# BinaryClock_LEDs.net
KiCad netlist of a schematic drawn in Altium Designer
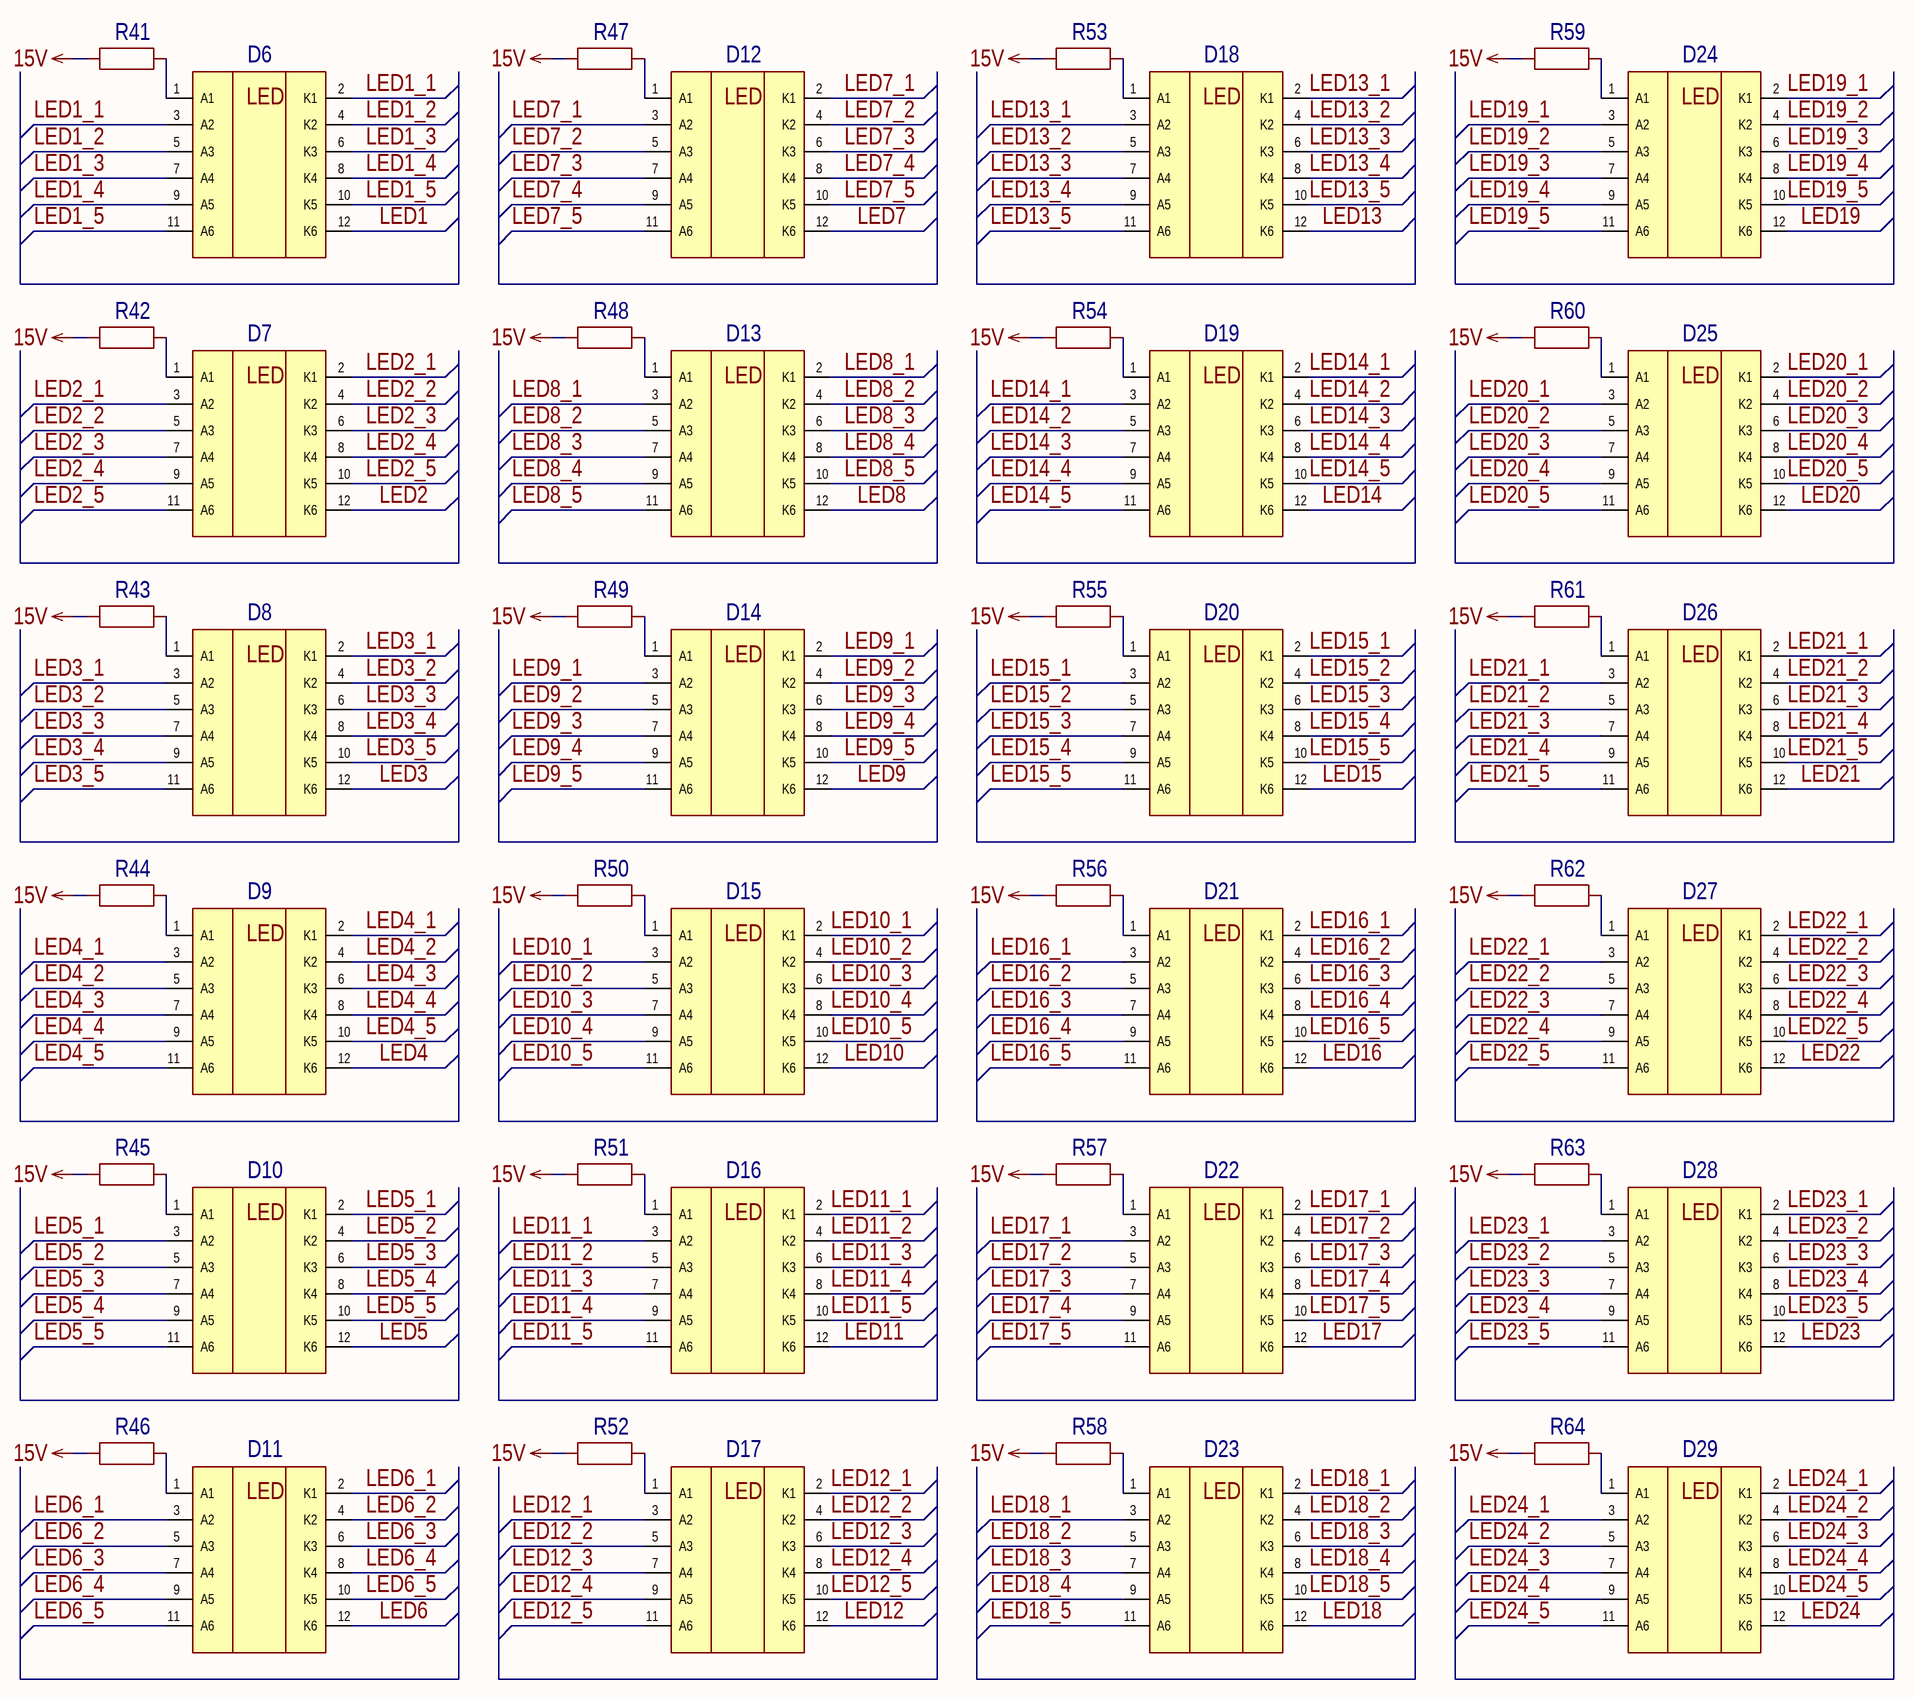
[diagram p0: BinaryClock_LEDs.SchDoc]

(export (version "E")
  (design (tool "Eeschema 10.0.6"))
  (components
    (comp (ref "D6")
      (value "DLA/6ID")
      (footprint "DLA/6ID")
      (description "20mm BIG LAMP")
      (fields (field (name "MANUFACTURER") "Kingbright"))
      (libsource (lib "Devices") (part "DLA"))
    )
    (comp (ref "D7")
      (value "DLA/6ID")
      (footprint "DLA/6ID")
      (description "20mm BIG LAMP")
      (fields (field (name "MANUFACTURER") "Kingbright"))
      (libsource (lib "Devices") (part "DLA"))
    )
    (comp (ref "D8")
      (value "DLA/6ID")
      (footprint "DLA/6ID")
      (description "20mm BIG LAMP")
      (fields (field (name "MANUFACTURER") "Kingbright"))
      (libsource (lib "Devices") (part "DLA"))
    )
    (comp (ref "D9")
      (value "DLA/6ID")
      (footprint "DLA/6ID")
      (description "20mm BIG LAMP")
      (fields (field (name "MANUFACTURER") "Kingbright"))
      (libsource (lib "Devices") (part "DLA"))
    )
    (comp (ref "D10")
      (value "DLA/6ID")
      (footprint "DLA/6ID")
      (description "20mm BIG LAMP")
      (fields (field (name "MANUFACTURER") "Kingbright"))
      (libsource (lib "Devices") (part "DLA"))
    )
    (comp (ref "D11")
      (value "DLA/6ID")
      (footprint "DLA/6ID")
      (description "20mm BIG LAMP")
      (fields (field (name "MANUFACTURER") "Kingbright"))
      (libsource (lib "Devices") (part "DLA"))
    )
    (comp (ref "D12")
      (value "DLA/6ID")
      (footprint "DLA/6ID")
      (description "20mm BIG LAMP")
      (fields (field (name "MANUFACTURER") "Kingbright"))
      (libsource (lib "Devices") (part "DLA"))
    )
    (comp (ref "D13")
      (value "DLA/6ID")
      (footprint "DLA/6ID")
      (description "20mm BIG LAMP")
      (fields (field (name "MANUFACTURER") "Kingbright"))
      (libsource (lib "Devices") (part "DLA"))
    )
    (comp (ref "D14")
      (value "DLA/6YD")
      (footprint "DLA/6YD")
      (description "20mm BIG LAMP")
      (fields (field (name "MANUFACTURER") "Kingbright"))
      (libsource (lib "Devices") (part "DLA"))
    )
    (comp (ref "D15")
      (value "DLA/6YD")
      (footprint "DLA/6YD")
      (description "20mm BIG LAMP")
      (fields (field (name "MANUFACTURER") "Kingbright"))
      (libsource (lib "Devices") (part "DLA"))
    )
    (comp (ref "D16")
      (value "DLA/6YD")
      (footprint "DLA/6YD")
      (description "20mm BIG LAMP")
      (fields (field (name "MANUFACTURER") "Kingbright"))
      (libsource (lib "Devices") (part "DLA"))
    )
    (comp (ref "D17")
      (value "DLA/6YD")
      (footprint "DLA/6YD")
      (description "20mm BIG LAMP")
      (fields (field (name "MANUFACTURER") "Kingbright"))
      (libsource (lib "Devices") (part "DLA"))
    )
    (comp (ref "D18")
      (value "DLA/6YD")
      (footprint "DLA/6YD")
      (description "20mm BIG LAMP")
      (fields (field (name "MANUFACTURER") "Kingbright"))
      (libsource (lib "Devices") (part "DLA"))
    )
    (comp (ref "D19")
      (value "DLA/6YD")
      (footprint "DLA/6YD")
      (description "20mm BIG LAMP")
      (fields (field (name "MANUFACTURER") "Kingbright"))
      (libsource (lib "Devices") (part "DLA"))
    )
    (comp (ref "D20")
      (value "DLA/6YD")
      (footprint "DLA/6YD")
      (description "20mm BIG LAMP")
      (fields (field (name "MANUFACTURER") "Kingbright"))
      (libsource (lib "Devices") (part "DLA"))
    )
    (comp (ref "D21")
      (value "DLA/6YD")
      (footprint "DLA/6YD")
      (description "20mm BIG LAMP")
      (fields (field (name "MANUFACTURER") "Kingbright"))
      (libsource (lib "Devices") (part "DLA"))
    )
    (comp (ref "D22")
      (value "DLA/6SGD")
      (footprint "DLA/6GD")
      (description "20mm BIG LAMP")
      (fields (field (name "MANUFACTURER") "Kingbright"))
      (libsource (lib "Devices") (part "DLA"))
    )
    (comp (ref "D23")
      (value "DLA/6SGD")
      (footprint "DLA/6GD")
      (description "20mm BIG LAMP")
      (fields (field (name "MANUFACTURER") "Kingbright"))
      (libsource (lib "Devices") (part "DLA"))
    )
    (comp (ref "D24")
      (value "DLA/6SGD")
      (footprint "DLA/6GD")
      (description "20mm BIG LAMP")
      (fields (field (name "MANUFACTURER") "Kingbright"))
      (libsource (lib "Devices") (part "DLA"))
    )
    (comp (ref "D25")
      (value "DLA/6SGD")
      (footprint "DLA/6GD")
      (description "20mm BIG LAMP")
      (fields (field (name "MANUFACTURER") "Kingbright"))
      (libsource (lib "Devices") (part "DLA"))
    )
    (comp (ref "D26")
      (value "DLA/6SGD")
      (footprint "DLA/6GD")
      (description "20mm BIG LAMP")
      (fields (field (name "MANUFACTURER") "Kingbright"))
      (libsource (lib "Devices") (part "DLA"))
    )
    (comp (ref "D27")
      (value "DLA/6SGD")
      (footprint "DLA/6GD")
      (description "20mm BIG LAMP")
      (fields (field (name "MANUFACTURER") "Kingbright"))
      (libsource (lib "Devices") (part "DLA"))
    )
    (comp (ref "D28")
      (value "DLA/6SGD")
      (footprint "DLA/6GD")
      (description "20mm BIG LAMP")
      (fields (field (name "MANUFACTURER") "Kingbright"))
      (libsource (lib "Devices") (part "DLA"))
    )
    (comp (ref "D29")
      (value "DLA/6SGD")
      (footprint "DLA/6GD")
      (description "20mm BIG LAMP")
      (fields (field (name "MANUFACTURER") "Kingbright"))
      (libsource (lib "Devices") (part "DLA"))
    )
    (comp (ref "R41")
      (value "0805±1 %-? kOhm")
      (footprint "SMD-0805-RES")
      (description "Resistor")
      (libsource (lib "Passive,Diodes") (part "Res"))
    )
    (comp (ref "R42")
      (value "0805±1 %-? kOhm")
      (footprint "SMD-0805-RES")
      (description "Resistor")
      (libsource (lib "Passive,Diodes") (part "Res"))
    )
    (comp (ref "R43")
      (value "0805±1 %-? kOhm")
      (footprint "SMD-0805-RES")
      (description "Resistor")
      (libsource (lib "Passive,Diodes") (part "Res"))
    )
    (comp (ref "R44")
      (value "0805±1 %-? kOhm")
      (footprint "SMD-0805-RES")
      (description "Resistor")
      (libsource (lib "Passive,Diodes") (part "Res"))
    )
    (comp (ref "R45")
      (value "0805±1 %-? kOhm")
      (footprint "SMD-0805-RES")
      (description "Resistor")
      (libsource (lib "Passive,Diodes") (part "Res"))
    )
    (comp (ref "R46")
      (value "0805±1 %-? kOhm")
      (footprint "SMD-0805-RES")
      (description "Resistor")
      (libsource (lib "Passive,Diodes") (part "Res"))
    )
    (comp (ref "R47")
      (value "0805±1 %-? kOhm")
      (footprint "SMD-0805-RES")
      (description "Resistor")
      (libsource (lib "Passive,Diodes") (part "Res"))
    )
    (comp (ref "R48")
      (value "0805±1 %-? kOhm")
      (footprint "SMD-0805-RES")
      (description "Resistor")
      (libsource (lib "Passive,Diodes") (part "Res"))
    )
    (comp (ref "R49")
      (value "0805±1 %-? kOhm")
      (footprint "SMD-0805-RES")
      (description "Resistor")
      (libsource (lib "Passive,Diodes") (part "Res"))
    )
    (comp (ref "R50")
      (value "0805±1 %-? kOhm")
      (footprint "SMD-0805-RES")
      (description "Resistor")
      (libsource (lib "Passive,Diodes") (part "Res"))
    )
    (comp (ref "R51")
      (value "0805±1 %-? kOhm")
      (footprint "SMD-0805-RES")
      (description "Resistor")
      (libsource (lib "Passive,Diodes") (part "Res"))
    )
    (comp (ref "R52")
      (value "0805±1 %-? kOhm")
      (footprint "SMD-0805-RES")
      (description "Resistor")
      (libsource (lib "Passive,Diodes") (part "Res"))
    )
    (comp (ref "R53")
      (value "0805±1 %-? kOhm")
      (footprint "SMD-0805-RES")
      (description "Resistor")
      (libsource (lib "Passive,Diodes") (part "Res"))
    )
    (comp (ref "R54")
      (value "0805±1 %-? kOhm")
      (footprint "SMD-0805-RES")
      (description "Resistor")
      (libsource (lib "Passive,Diodes") (part "Res"))
    )
    (comp (ref "R55")
      (value "0805±1 %-? kOhm")
      (footprint "SMD-0805-RES")
      (description "Resistor")
      (libsource (lib "Passive,Diodes") (part "Res"))
    )
    (comp (ref "R56")
      (value "0805±1 %-? kOhm")
      (footprint "SMD-0805-RES")
      (description "Resistor")
      (libsource (lib "Passive,Diodes") (part "Res"))
    )
    (comp (ref "R57")
      (value "0805±1 %-? kOhm")
      (footprint "SMD-0805-RES")
      (description "Resistor")
      (libsource (lib "Passive,Diodes") (part "Res"))
    )
    (comp (ref "R58")
      (value "0805±1 %-? kOhm")
      (footprint "SMD-0805-RES")
      (description "Resistor")
      (libsource (lib "Passive,Diodes") (part "Res"))
    )
    (comp (ref "R59")
      (value "0805±1 %-? kOhm")
      (footprint "SMD-0805-RES")
      (description "Resistor")
      (libsource (lib "Passive,Diodes") (part "Res"))
    )
    (comp (ref "R60")
      (value "0805±1 %-? kOhm")
      (footprint "SMD-0805-RES")
      (description "Resistor")
      (libsource (lib "Passive,Diodes") (part "Res"))
    )
    (comp (ref "R61")
      (value "0805±1 %-? kOhm")
      (footprint "SMD-0805-RES")
      (description "Resistor")
      (libsource (lib "Passive,Diodes") (part "Res"))
    )
    (comp (ref "R62")
      (value "0805±1 %-? kOhm")
      (footprint "SMD-0805-RES")
      (description "Resistor")
      (libsource (lib "Passive,Diodes") (part "Res"))
    )
    (comp (ref "R63")
      (value "0805±1 %-? kOhm")
      (footprint "SMD-0805-RES")
      (description "Resistor")
      (libsource (lib "Passive,Diodes") (part "Res"))
    )
    (comp (ref "R64")
      (value "0805±1 %-? kOhm")
      (footprint "SMD-0805-RES")
      (description "Resistor")
      (libsource (lib "Passive,Diodes") (part "Res"))
    )
  )
  (nets
    (net (code "1") (name "/LED1") (class "Default")
      (node (ref "D6") (pin "12") (pinfunction "K6_12") (pintype "passive"))
    )
    (net (code "2") (name "/LED1_1") (class "Default")
      (node (ref "D6") (pin "2") (pinfunction "K1_2") (pintype "passive"))
      (node (ref "D6") (pin "3") (pinfunction "A2_3") (pintype "passive"))
    )
    (net (code "3") (name "/LED1_2") (class "Default")
      (node (ref "D6") (pin "4") (pinfunction "K2_4") (pintype "passive"))
      (node (ref "D6") (pin "5") (pinfunction "A3_5") (pintype "passive"))
    )
    (net (code "4") (name "/LED1_3") (class "Default")
      (node (ref "D6") (pin "6") (pinfunction "K3_6") (pintype "passive"))
      (node (ref "D6") (pin "7") (pinfunction "A4_7") (pintype "passive"))
    )
    (net (code "5") (name "/LED1_4") (class "Default")
      (node (ref "D6") (pin "8") (pinfunction "K4_8") (pintype "passive"))
      (node (ref "D6") (pin "9") (pinfunction "A5_9") (pintype "passive"))
    )
    (net (code "6") (name "/LED1_5") (class "Default")
      (node (ref "D6") (pin "10") (pinfunction "K5_10") (pintype "passive"))
      (node (ref "D6") (pin "11") (pinfunction "A6_11") (pintype "passive"))
    )
    (net (code "7") (name "/LED2") (class "Default")
      (node (ref "D7") (pin "12") (pinfunction "K6_12") (pintype "passive"))
    )
    (net (code "8") (name "/LED2_1") (class "Default")
      (node (ref "D7") (pin "2") (pinfunction "K1_2") (pintype "passive"))
      (node (ref "D7") (pin "3") (pinfunction "A2_3") (pintype "passive"))
    )
    (net (code "9") (name "/LED2_2") (class "Default")
      (node (ref "D7") (pin "4") (pinfunction "K2_4") (pintype "passive"))
      (node (ref "D7") (pin "5") (pinfunction "A3_5") (pintype "passive"))
    )
    (net (code "10") (name "/LED2_3") (class "Default")
      (node (ref "D7") (pin "6") (pinfunction "K3_6") (pintype "passive"))
      (node (ref "D7") (pin "7") (pinfunction "A4_7") (pintype "passive"))
    )
    (net (code "11") (name "/LED2_4") (class "Default")
      (node (ref "D7") (pin "8") (pinfunction "K4_8") (pintype "passive"))
      (node (ref "D7") (pin "9") (pinfunction "A5_9") (pintype "passive"))
    )
    (net (code "12") (name "/LED2_5") (class "Default")
      (node (ref "D7") (pin "10") (pinfunction "K5_10") (pintype "passive"))
      (node (ref "D7") (pin "11") (pinfunction "A6_11") (pintype "passive"))
    )
    (net (code "13") (name "/LED3") (class "Default")
      (node (ref "D8") (pin "12") (pinfunction "K6_12") (pintype "passive"))
    )
    (net (code "14") (name "/LED3_1") (class "Default")
      (node (ref "D8") (pin "2") (pinfunction "K1_2") (pintype "passive"))
      (node (ref "D8") (pin "3") (pinfunction "A2_3") (pintype "passive"))
    )
    (net (code "15") (name "/LED3_2") (class "Default")
      (node (ref "D8") (pin "4") (pinfunction "K2_4") (pintype "passive"))
      (node (ref "D8") (pin "5") (pinfunction "A3_5") (pintype "passive"))
    )
    (net (code "16") (name "/LED3_3") (class "Default")
      (node (ref "D8") (pin "6") (pinfunction "K3_6") (pintype "passive"))
      (node (ref "D8") (pin "7") (pinfunction "A4_7") (pintype "passive"))
    )
    (net (code "17") (name "/LED3_4") (class "Default")
      (node (ref "D8") (pin "8") (pinfunction "K4_8") (pintype "passive"))
      (node (ref "D8") (pin "9") (pinfunction "A5_9") (pintype "passive"))
    )
    (net (code "18") (name "/LED3_5") (class "Default")
      (node (ref "D8") (pin "10") (pinfunction "K5_10") (pintype "passive"))
      (node (ref "D8") (pin "11") (pinfunction "A6_11") (pintype "passive"))
    )
    (net (code "19") (name "/LED4") (class "Default")
      (node (ref "D9") (pin "12") (pinfunction "K6_12") (pintype "passive"))
    )
    (net (code "20") (name "/LED4_1") (class "Default")
      (node (ref "D9") (pin "2") (pinfunction "K1_2") (pintype "passive"))
      (node (ref "D9") (pin "3") (pinfunction "A2_3") (pintype "passive"))
    )
    (net (code "21") (name "/LED4_2") (class "Default")
      (node (ref "D9") (pin "4") (pinfunction "K2_4") (pintype "passive"))
      (node (ref "D9") (pin "5") (pinfunction "A3_5") (pintype "passive"))
    )
    (net (code "22") (name "/LED4_3") (class "Default")
      (node (ref "D9") (pin "6") (pinfunction "K3_6") (pintype "passive"))
      (node (ref "D9") (pin "7") (pinfunction "A4_7") (pintype "passive"))
    )
    (net (code "23") (name "/LED4_4") (class "Default")
      (node (ref "D9") (pin "8") (pinfunction "K4_8") (pintype "passive"))
      (node (ref "D9") (pin "9") (pinfunction "A5_9") (pintype "passive"))
    )
    (net (code "24") (name "/LED4_5") (class "Default")
      (node (ref "D9") (pin "10") (pinfunction "K5_10") (pintype "passive"))
      (node (ref "D9") (pin "11") (pinfunction "A6_11") (pintype "passive"))
    )
    (net (code "25") (name "/LED5") (class "Default")
      (node (ref "D10") (pin "12") (pinfunction "K6_12") (pintype "passive"))
    )
    (net (code "26") (name "/LED5_1") (class "Default")
      (node (ref "D10") (pin "2") (pinfunction "K1_2") (pintype "passive"))
      (node (ref "D10") (pin "3") (pinfunction "A2_3") (pintype "passive"))
    )
    (net (code "27") (name "/LED5_2") (class "Default")
      (node (ref "D10") (pin "4") (pinfunction "K2_4") (pintype "passive"))
      (node (ref "D10") (pin "5") (pinfunction "A3_5") (pintype "passive"))
    )
    (net (code "28") (name "/LED5_3") (class "Default")
      (node (ref "D10") (pin "6") (pinfunction "K3_6") (pintype "passive"))
      (node (ref "D10") (pin "7") (pinfunction "A4_7") (pintype "passive"))
    )
    (net (code "29") (name "/LED5_4") (class "Default")
      (node (ref "D10") (pin "8") (pinfunction "K4_8") (pintype "passive"))
      (node (ref "D10") (pin "9") (pinfunction "A5_9") (pintype "passive"))
    )
    (net (code "30") (name "/LED5_5") (class "Default")
      (node (ref "D10") (pin "10") (pinfunction "K5_10") (pintype "passive"))
      (node (ref "D10") (pin "11") (pinfunction "A6_11") (pintype "passive"))
    )
    (net (code "31") (name "/LED6") (class "Default")
      (node (ref "D11") (pin "12") (pinfunction "K6_12") (pintype "passive"))
    )
    (net (code "32") (name "/LED6_1") (class "Default")
      (node (ref "D11") (pin "2") (pinfunction "K1_2") (pintype "passive"))
      (node (ref "D11") (pin "3") (pinfunction "A2_3") (pintype "passive"))
    )
    (net (code "33") (name "/LED6_2") (class "Default")
      (node (ref "D11") (pin "4") (pinfunction "K2_4") (pintype "passive"))
      (node (ref "D11") (pin "5") (pinfunction "A3_5") (pintype "passive"))
    )
    (net (code "34") (name "/LED6_3") (class "Default")
      (node (ref "D11") (pin "6") (pinfunction "K3_6") (pintype "passive"))
      (node (ref "D11") (pin "7") (pinfunction "A4_7") (pintype "passive"))
    )
    (net (code "35") (name "/LED6_4") (class "Default")
      (node (ref "D11") (pin "8") (pinfunction "K4_8") (pintype "passive"))
      (node (ref "D11") (pin "9") (pinfunction "A5_9") (pintype "passive"))
    )
    (net (code "36") (name "/LED6_5") (class "Default")
      (node (ref "D11") (pin "10") (pinfunction "K5_10") (pintype "passive"))
      (node (ref "D11") (pin "11") (pinfunction "A6_11") (pintype "passive"))
    )
    (net (code "37") (name "/LED7") (class "Default")
      (node (ref "D12") (pin "12") (pinfunction "K6_12") (pintype "passive"))
    )
    (net (code "38") (name "/LED7_1") (class "Default")
      (node (ref "D12") (pin "2") (pinfunction "K1_2") (pintype "passive"))
      (node (ref "D12") (pin "3") (pinfunction "A2_3") (pintype "passive"))
    )
    (net (code "39") (name "/LED7_2") (class "Default")
      (node (ref "D12") (pin "4") (pinfunction "K2_4") (pintype "passive"))
      (node (ref "D12") (pin "5") (pinfunction "A3_5") (pintype "passive"))
    )
    (net (code "40") (name "/LED7_3") (class "Default")
      (node (ref "D12") (pin "6") (pinfunction "K3_6") (pintype "passive"))
      (node (ref "D12") (pin "7") (pinfunction "A4_7") (pintype "passive"))
    )
    (net (code "41") (name "/LED7_4") (class "Default")
      (node (ref "D12") (pin "8") (pinfunction "K4_8") (pintype "passive"))
      (node (ref "D12") (pin "9") (pinfunction "A5_9") (pintype "passive"))
    )
    (net (code "42") (name "/LED7_5") (class "Default")
      (node (ref "D12") (pin "10") (pinfunction "K5_10") (pintype "passive"))
      (node (ref "D12") (pin "11") (pinfunction "A6_11") (pintype "passive"))
    )
    (net (code "43") (name "/LED8") (class "Default")
      (node (ref "D13") (pin "12") (pinfunction "K6_12") (pintype "passive"))
    )
    (net (code "44") (name "/LED8_1") (class "Default")
      (node (ref "D13") (pin "2") (pinfunction "K1_2") (pintype "passive"))
      (node (ref "D13") (pin "3") (pinfunction "A2_3") (pintype "passive"))
    )
    (net (code "45") (name "/LED8_2") (class "Default")
      (node (ref "D13") (pin "4") (pinfunction "K2_4") (pintype "passive"))
      (node (ref "D13") (pin "5") (pinfunction "A3_5") (pintype "passive"))
    )
    (net (code "46") (name "/LED8_3") (class "Default")
      (node (ref "D13") (pin "6") (pinfunction "K3_6") (pintype "passive"))
      (node (ref "D13") (pin "7") (pinfunction "A4_7") (pintype "passive"))
    )
    (net (code "47") (name "/LED8_4") (class "Default")
      (node (ref "D13") (pin "8") (pinfunction "K4_8") (pintype "passive"))
      (node (ref "D13") (pin "9") (pinfunction "A5_9") (pintype "passive"))
    )
    (net (code "48") (name "/LED8_5") (class "Default")
      (node (ref "D13") (pin "10") (pinfunction "K5_10") (pintype "passive"))
      (node (ref "D13") (pin "11") (pinfunction "A6_11") (pintype "passive"))
    )
    (net (code "49") (name "/LED9") (class "Default")
      (node (ref "D14") (pin "12") (pinfunction "K6_12") (pintype "passive"))
    )
    (net (code "50") (name "/LED9_1") (class "Default")
      (node (ref "D14") (pin "2") (pinfunction "K1_2") (pintype "passive"))
      (node (ref "D14") (pin "3") (pinfunction "A2_3") (pintype "passive"))
    )
    (net (code "51") (name "/LED9_2") (class "Default")
      (node (ref "D14") (pin "4") (pinfunction "K2_4") (pintype "passive"))
      (node (ref "D14") (pin "5") (pinfunction "A3_5") (pintype "passive"))
    )
    (net (code "52") (name "/LED9_3") (class "Default")
      (node (ref "D14") (pin "6") (pinfunction "K3_6") (pintype "passive"))
      (node (ref "D14") (pin "7") (pinfunction "A4_7") (pintype "passive"))
    )
    (net (code "53") (name "/LED9_4") (class "Default")
      (node (ref "D14") (pin "8") (pinfunction "K4_8") (pintype "passive"))
      (node (ref "D14") (pin "9") (pinfunction "A5_9") (pintype "passive"))
    )
    (net (code "54") (name "/LED9_5") (class "Default")
      (node (ref "D14") (pin "10") (pinfunction "K5_10") (pintype "passive"))
      (node (ref "D14") (pin "11") (pinfunction "A6_11") (pintype "passive"))
    )
    (net (code "55") (name "/LED10") (class "Default")
      (node (ref "D15") (pin "12") (pinfunction "K6_12") (pintype "passive"))
    )
    (net (code "56") (name "/LED10_1") (class "Default")
      (node (ref "D15") (pin "2") (pinfunction "K1_2") (pintype "passive"))
      (node (ref "D15") (pin "3") (pinfunction "A2_3") (pintype "passive"))
    )
    (net (code "57") (name "/LED10_2") (class "Default")
      (node (ref "D15") (pin "4") (pinfunction "K2_4") (pintype "passive"))
      (node (ref "D15") (pin "5") (pinfunction "A3_5") (pintype "passive"))
    )
    (net (code "58") (name "/LED10_3") (class "Default")
      (node (ref "D15") (pin "6") (pinfunction "K3_6") (pintype "passive"))
      (node (ref "D15") (pin "7") (pinfunction "A4_7") (pintype "passive"))
    )
    (net (code "59") (name "/LED10_4") (class "Default")
      (node (ref "D15") (pin "8") (pinfunction "K4_8") (pintype "passive"))
      (node (ref "D15") (pin "9") (pinfunction "A5_9") (pintype "passive"))
    )
    (net (code "60") (name "/LED10_5") (class "Default")
      (node (ref "D15") (pin "10") (pinfunction "K5_10") (pintype "passive"))
      (node (ref "D15") (pin "11") (pinfunction "A6_11") (pintype "passive"))
    )
    (net (code "61") (name "/LED11") (class "Default")
      (node (ref "D16") (pin "12") (pinfunction "K6_12") (pintype "passive"))
    )
    (net (code "62") (name "/LED11_1") (class "Default")
      (node (ref "D16") (pin "2") (pinfunction "K1_2") (pintype "passive"))
      (node (ref "D16") (pin "3") (pinfunction "A2_3") (pintype "passive"))
    )
    (net (code "63") (name "/LED11_2") (class "Default")
      (node (ref "D16") (pin "4") (pinfunction "K2_4") (pintype "passive"))
      (node (ref "D16") (pin "5") (pinfunction "A3_5") (pintype "passive"))
    )
    (net (code "64") (name "/LED11_3") (class "Default")
      (node (ref "D16") (pin "6") (pinfunction "K3_6") (pintype "passive"))
      (node (ref "D16") (pin "7") (pinfunction "A4_7") (pintype "passive"))
    )
    (net (code "65") (name "/LED11_4") (class "Default")
      (node (ref "D16") (pin "8") (pinfunction "K4_8") (pintype "passive"))
      (node (ref "D16") (pin "9") (pinfunction "A5_9") (pintype "passive"))
    )
    (net (code "66") (name "/LED11_5") (class "Default")
      (node (ref "D16") (pin "10") (pinfunction "K5_10") (pintype "passive"))
      (node (ref "D16") (pin "11") (pinfunction "A6_11") (pintype "passive"))
    )
    (net (code "67") (name "/LED12") (class "Default")
      (node (ref "D17") (pin "12") (pinfunction "K6_12") (pintype "passive"))
    )
    (net (code "68") (name "/LED12_1") (class "Default")
      (node (ref "D17") (pin "2") (pinfunction "K1_2") (pintype "passive"))
      (node (ref "D17") (pin "3") (pinfunction "A2_3") (pintype "passive"))
    )
    (net (code "69") (name "/LED12_2") (class "Default")
      (node (ref "D17") (pin "4") (pinfunction "K2_4") (pintype "passive"))
      (node (ref "D17") (pin "5") (pinfunction "A3_5") (pintype "passive"))
    )
    (net (code "70") (name "/LED12_3") (class "Default")
      (node (ref "D17") (pin "6") (pinfunction "K3_6") (pintype "passive"))
      (node (ref "D17") (pin "7") (pinfunction "A4_7") (pintype "passive"))
    )
    (net (code "71") (name "/LED12_4") (class "Default")
      (node (ref "D17") (pin "8") (pinfunction "K4_8") (pintype "passive"))
      (node (ref "D17") (pin "9") (pinfunction "A5_9") (pintype "passive"))
    )
    (net (code "72") (name "/LED12_5") (class "Default")
      (node (ref "D17") (pin "10") (pinfunction "K5_10") (pintype "passive"))
      (node (ref "D17") (pin "11") (pinfunction "A6_11") (pintype "passive"))
    )
    (net (code "73") (name "/LED13") (class "Default")
      (node (ref "D18") (pin "12") (pinfunction "K6_12") (pintype "passive"))
    )
    (net (code "74") (name "/LED13_1") (class "Default")
      (node (ref "D18") (pin "2") (pinfunction "K1_2") (pintype "passive"))
      (node (ref "D18") (pin "3") (pinfunction "A2_3") (pintype "passive"))
    )
    (net (code "75") (name "/LED13_2") (class "Default")
      (node (ref "D18") (pin "4") (pinfunction "K2_4") (pintype "passive"))
      (node (ref "D18") (pin "5") (pinfunction "A3_5") (pintype "passive"))
    )
    (net (code "76") (name "/LED13_3") (class "Default")
      (node (ref "D18") (pin "6") (pinfunction "K3_6") (pintype "passive"))
      (node (ref "D18") (pin "7") (pinfunction "A4_7") (pintype "passive"))
    )
    (net (code "77") (name "/LED13_4") (class "Default")
      (node (ref "D18") (pin "8") (pinfunction "K4_8") (pintype "passive"))
      (node (ref "D18") (pin "9") (pinfunction "A5_9") (pintype "passive"))
    )
    (net (code "78") (name "/LED13_5") (class "Default")
      (node (ref "D18") (pin "10") (pinfunction "K5_10") (pintype "passive"))
      (node (ref "D18") (pin "11") (pinfunction "A6_11") (pintype "passive"))
    )
    (net (code "79") (name "/LED14") (class "Default")
      (node (ref "D19") (pin "12") (pinfunction "K6_12") (pintype "passive"))
    )
    (net (code "80") (name "/LED14_1") (class "Default")
      (node (ref "D19") (pin "2") (pinfunction "K1_2") (pintype "passive"))
      (node (ref "D19") (pin "3") (pinfunction "A2_3") (pintype "passive"))
    )
    (net (code "81") (name "/LED14_2") (class "Default")
      (node (ref "D19") (pin "4") (pinfunction "K2_4") (pintype "passive"))
      (node (ref "D19") (pin "5") (pinfunction "A3_5") (pintype "passive"))
    )
    (net (code "82") (name "/LED14_3") (class "Default")
      (node (ref "D19") (pin "6") (pinfunction "K3_6") (pintype "passive"))
      (node (ref "D19") (pin "7") (pinfunction "A4_7") (pintype "passive"))
    )
    (net (code "83") (name "/LED14_4") (class "Default")
      (node (ref "D19") (pin "8") (pinfunction "K4_8") (pintype "passive"))
      (node (ref "D19") (pin "9") (pinfunction "A5_9") (pintype "passive"))
    )
    (net (code "84") (name "/LED14_5") (class "Default")
      (node (ref "D19") (pin "10") (pinfunction "K5_10") (pintype "passive"))
      (node (ref "D19") (pin "11") (pinfunction "A6_11") (pintype "passive"))
    )
    (net (code "85") (name "/LED15") (class "Default")
      (node (ref "D20") (pin "12") (pinfunction "K6_12") (pintype "passive"))
    )
    (net (code "86") (name "/LED15_1") (class "Default")
      (node (ref "D20") (pin "2") (pinfunction "K1_2") (pintype "passive"))
      (node (ref "D20") (pin "3") (pinfunction "A2_3") (pintype "passive"))
    )
    (net (code "87") (name "/LED15_2") (class "Default")
      (node (ref "D20") (pin "4") (pinfunction "K2_4") (pintype "passive"))
      (node (ref "D20") (pin "5") (pinfunction "A3_5") (pintype "passive"))
    )
    (net (code "88") (name "/LED15_3") (class "Default")
      (node (ref "D20") (pin "6") (pinfunction "K3_6") (pintype "passive"))
      (node (ref "D20") (pin "7") (pinfunction "A4_7") (pintype "passive"))
    )
    (net (code "89") (name "/LED15_4") (class "Default")
      (node (ref "D20") (pin "8") (pinfunction "K4_8") (pintype "passive"))
      (node (ref "D20") (pin "9") (pinfunction "A5_9") (pintype "passive"))
    )
    (net (code "90") (name "/LED15_5") (class "Default")
      (node (ref "D20") (pin "10") (pinfunction "K5_10") (pintype "passive"))
      (node (ref "D20") (pin "11") (pinfunction "A6_11") (pintype "passive"))
    )
    (net (code "91") (name "/LED16") (class "Default")
      (node (ref "D21") (pin "12") (pinfunction "K6_12") (pintype "passive"))
    )
    (net (code "92") (name "/LED16_1") (class "Default")
      (node (ref "D21") (pin "2") (pinfunction "K1_2") (pintype "passive"))
      (node (ref "D21") (pin "3") (pinfunction "A2_3") (pintype "passive"))
    )
    (net (code "93") (name "/LED16_2") (class "Default")
      (node (ref "D21") (pin "4") (pinfunction "K2_4") (pintype "passive"))
      (node (ref "D21") (pin "5") (pinfunction "A3_5") (pintype "passive"))
    )
    (net (code "94") (name "/LED16_3") (class "Default")
      (node (ref "D21") (pin "6") (pinfunction "K3_6") (pintype "passive"))
      (node (ref "D21") (pin "7") (pinfunction "A4_7") (pintype "passive"))
    )
    (net (code "95") (name "/LED16_4") (class "Default")
      (node (ref "D21") (pin "8") (pinfunction "K4_8") (pintype "passive"))
      (node (ref "D21") (pin "9") (pinfunction "A5_9") (pintype "passive"))
    )
    (net (code "96") (name "/LED16_5") (class "Default")
      (node (ref "D21") (pin "10") (pinfunction "K5_10") (pintype "passive"))
      (node (ref "D21") (pin "11") (pinfunction "A6_11") (pintype "passive"))
    )
    (net (code "97") (name "/LED17") (class "Default")
      (node (ref "D22") (pin "12") (pinfunction "K6_12") (pintype "passive"))
    )
    (net (code "98") (name "/LED17_1") (class "Default")
      (node (ref "D22") (pin "2") (pinfunction "K1_2") (pintype "passive"))
      (node (ref "D22") (pin "3") (pinfunction "A2_3") (pintype "passive"))
    )
    (net (code "99") (name "/LED17_2") (class "Default")
      (node (ref "D22") (pin "4") (pinfunction "K2_4") (pintype "passive"))
      (node (ref "D22") (pin "5") (pinfunction "A3_5") (pintype "passive"))
    )
    (net (code "100") (name "/LED17_3") (class "Default")
      (node (ref "D22") (pin "6") (pinfunction "K3_6") (pintype "passive"))
      (node (ref "D22") (pin "7") (pinfunction "A4_7") (pintype "passive"))
    )
    (net (code "101") (name "/LED17_4") (class "Default")
      (node (ref "D22") (pin "8") (pinfunction "K4_8") (pintype "passive"))
      (node (ref "D22") (pin "9") (pinfunction "A5_9") (pintype "passive"))
    )
    (net (code "102") (name "/LED17_5") (class "Default")
      (node (ref "D22") (pin "10") (pinfunction "K5_10") (pintype "passive"))
      (node (ref "D22") (pin "11") (pinfunction "A6_11") (pintype "passive"))
    )
    (net (code "103") (name "/LED18") (class "Default")
      (node (ref "D23") (pin "12") (pinfunction "K6_12") (pintype "passive"))
    )
    (net (code "104") (name "/LED18_1") (class "Default")
      (node (ref "D23") (pin "2") (pinfunction "K1_2") (pintype "passive"))
      (node (ref "D23") (pin "3") (pinfunction "A2_3") (pintype "passive"))
    )
    (net (code "105") (name "/LED18_2") (class "Default")
      (node (ref "D23") (pin "4") (pinfunction "K2_4") (pintype "passive"))
      (node (ref "D23") (pin "5") (pinfunction "A3_5") (pintype "passive"))
    )
    (net (code "106") (name "/LED18_3") (class "Default")
      (node (ref "D23") (pin "6") (pinfunction "K3_6") (pintype "passive"))
      (node (ref "D23") (pin "7") (pinfunction "A4_7") (pintype "passive"))
    )
    (net (code "107") (name "/LED18_4") (class "Default")
      (node (ref "D23") (pin "8") (pinfunction "K4_8") (pintype "passive"))
      (node (ref "D23") (pin "9") (pinfunction "A5_9") (pintype "passive"))
    )
    (net (code "108") (name "/LED18_5") (class "Default")
      (node (ref "D23") (pin "10") (pinfunction "K5_10") (pintype "passive"))
      (node (ref "D23") (pin "11") (pinfunction "A6_11") (pintype "passive"))
    )
    (net (code "109") (name "/LED19") (class "Default")
      (node (ref "D24") (pin "12") (pinfunction "K6_12") (pintype "passive"))
    )
    (net (code "110") (name "/LED19_1") (class "Default")
      (node (ref "D24") (pin "2") (pinfunction "K1_2") (pintype "passive"))
      (node (ref "D24") (pin "3") (pinfunction "A2_3") (pintype "passive"))
    )
    (net (code "111") (name "/LED19_2") (class "Default")
      (node (ref "D24") (pin "4") (pinfunction "K2_4") (pintype "passive"))
      (node (ref "D24") (pin "5") (pinfunction "A3_5") (pintype "passive"))
    )
    (net (code "112") (name "/LED19_3") (class "Default")
      (node (ref "D24") (pin "6") (pinfunction "K3_6") (pintype "passive"))
      (node (ref "D24") (pin "7") (pinfunction "A4_7") (pintype "passive"))
    )
    (net (code "113") (name "/LED19_4") (class "Default")
      (node (ref "D24") (pin "8") (pinfunction "K4_8") (pintype "passive"))
      (node (ref "D24") (pin "9") (pinfunction "A5_9") (pintype "passive"))
    )
    (net (code "114") (name "/LED19_5") (class "Default")
      (node (ref "D24") (pin "10") (pinfunction "K5_10") (pintype "passive"))
      (node (ref "D24") (pin "11") (pinfunction "A6_11") (pintype "passive"))
    )
    (net (code "115") (name "/LED20") (class "Default")
      (node (ref "D25") (pin "12") (pinfunction "K6_12") (pintype "passive"))
    )
    (net (code "116") (name "/LED20_1") (class "Default")
      (node (ref "D25") (pin "2") (pinfunction "K1_2") (pintype "passive"))
      (node (ref "D25") (pin "3") (pinfunction "A2_3") (pintype "passive"))
    )
    (net (code "117") (name "/LED20_2") (class "Default")
      (node (ref "D25") (pin "4") (pinfunction "K2_4") (pintype "passive"))
      (node (ref "D25") (pin "5") (pinfunction "A3_5") (pintype "passive"))
    )
    (net (code "118") (name "/LED20_3") (class "Default")
      (node (ref "D25") (pin "6") (pinfunction "K3_6") (pintype "passive"))
      (node (ref "D25") (pin "7") (pinfunction "A4_7") (pintype "passive"))
    )
    (net (code "119") (name "/LED20_4") (class "Default")
      (node (ref "D25") (pin "8") (pinfunction "K4_8") (pintype "passive"))
      (node (ref "D25") (pin "9") (pinfunction "A5_9") (pintype "passive"))
    )
    (net (code "120") (name "/LED20_5") (class "Default")
      (node (ref "D25") (pin "10") (pinfunction "K5_10") (pintype "passive"))
      (node (ref "D25") (pin "11") (pinfunction "A6_11") (pintype "passive"))
    )
    (net (code "121") (name "/LED21") (class "Default")
      (node (ref "D26") (pin "12") (pinfunction "K6_12") (pintype "passive"))
    )
    (net (code "122") (name "/LED21_1") (class "Default")
      (node (ref "D26") (pin "2") (pinfunction "K1_2") (pintype "passive"))
      (node (ref "D26") (pin "3") (pinfunction "A2_3") (pintype "passive"))
    )
    (net (code "123") (name "/LED21_2") (class "Default")
      (node (ref "D26") (pin "4") (pinfunction "K2_4") (pintype "passive"))
      (node (ref "D26") (pin "5") (pinfunction "A3_5") (pintype "passive"))
    )
    (net (code "124") (name "/LED21_3") (class "Default")
      (node (ref "D26") (pin "6") (pinfunction "K3_6") (pintype "passive"))
      (node (ref "D26") (pin "7") (pinfunction "A4_7") (pintype "passive"))
    )
    (net (code "125") (name "/LED21_4") (class "Default")
      (node (ref "D26") (pin "8") (pinfunction "K4_8") (pintype "passive"))
      (node (ref "D26") (pin "9") (pinfunction "A5_9") (pintype "passive"))
    )
    (net (code "126") (name "/LED21_5") (class "Default")
      (node (ref "D26") (pin "10") (pinfunction "K5_10") (pintype "passive"))
      (node (ref "D26") (pin "11") (pinfunction "A6_11") (pintype "passive"))
    )
    (net (code "127") (name "/LED22") (class "Default")
      (node (ref "D27") (pin "12") (pinfunction "K6_12") (pintype "passive"))
    )
    (net (code "128") (name "/LED22_1") (class "Default")
      (node (ref "D27") (pin "2") (pinfunction "K1_2") (pintype "passive"))
      (node (ref "D27") (pin "3") (pinfunction "A2_3") (pintype "passive"))
    )
    (net (code "129") (name "/LED22_2") (class "Default")
      (node (ref "D27") (pin "4") (pinfunction "K2_4") (pintype "passive"))
      (node (ref "D27") (pin "5") (pinfunction "A3_5") (pintype "passive"))
    )
    (net (code "130") (name "/LED22_3") (class "Default")
      (node (ref "D27") (pin "6") (pinfunction "K3_6") (pintype "passive"))
      (node (ref "D27") (pin "7") (pinfunction "A4_7") (pintype "passive"))
    )
    (net (code "131") (name "/LED22_4") (class "Default")
      (node (ref "D27") (pin "8") (pinfunction "K4_8") (pintype "passive"))
      (node (ref "D27") (pin "9") (pinfunction "A5_9") (pintype "passive"))
    )
    (net (code "132") (name "/LED22_5") (class "Default")
      (node (ref "D27") (pin "10") (pinfunction "K5_10") (pintype "passive"))
      (node (ref "D27") (pin "11") (pinfunction "A6_11") (pintype "passive"))
    )
    (net (code "133") (name "/LED23") (class "Default")
      (node (ref "D28") (pin "12") (pinfunction "K6_12") (pintype "passive"))
    )
    (net (code "134") (name "/LED23_1") (class "Default")
      (node (ref "D28") (pin "2") (pinfunction "K1_2") (pintype "passive"))
      (node (ref "D28") (pin "3") (pinfunction "A2_3") (pintype "passive"))
    )
    (net (code "135") (name "/LED23_2") (class "Default")
      (node (ref "D28") (pin "4") (pinfunction "K2_4") (pintype "passive"))
      (node (ref "D28") (pin "5") (pinfunction "A3_5") (pintype "passive"))
    )
    (net (code "136") (name "/LED23_3") (class "Default")
      (node (ref "D28") (pin "6") (pinfunction "K3_6") (pintype "passive"))
      (node (ref "D28") (pin "7") (pinfunction "A4_7") (pintype "passive"))
    )
    (net (code "137") (name "/LED23_4") (class "Default")
      (node (ref "D28") (pin "8") (pinfunction "K4_8") (pintype "passive"))
      (node (ref "D28") (pin "9") (pinfunction "A5_9") (pintype "passive"))
    )
    (net (code "138") (name "/LED23_5") (class "Default")
      (node (ref "D28") (pin "10") (pinfunction "K5_10") (pintype "passive"))
      (node (ref "D28") (pin "11") (pinfunction "A6_11") (pintype "passive"))
    )
    (net (code "139") (name "/LED24") (class "Default")
      (node (ref "D29") (pin "12") (pinfunction "K6_12") (pintype "passive"))
    )
    (net (code "140") (name "/LED24_1") (class "Default")
      (node (ref "D29") (pin "2") (pinfunction "K1_2") (pintype "passive"))
      (node (ref "D29") (pin "3") (pinfunction "A2_3") (pintype "passive"))
    )
    (net (code "141") (name "/LED24_2") (class "Default")
      (node (ref "D29") (pin "4") (pinfunction "K2_4") (pintype "passive"))
      (node (ref "D29") (pin "5") (pinfunction "A3_5") (pintype "passive"))
    )
    (net (code "142") (name "/LED24_3") (class "Default")
      (node (ref "D29") (pin "6") (pinfunction "K3_6") (pintype "passive"))
      (node (ref "D29") (pin "7") (pinfunction "A4_7") (pintype "passive"))
    )
    (net (code "143") (name "/LED24_4") (class "Default")
      (node (ref "D29") (pin "8") (pinfunction "K4_8") (pintype "passive"))
      (node (ref "D29") (pin "9") (pinfunction "A5_9") (pintype "passive"))
    )
    (net (code "144") (name "/LED24_5") (class "Default")
      (node (ref "D29") (pin "10") (pinfunction "K5_10") (pintype "passive"))
      (node (ref "D29") (pin "11") (pinfunction "A6_11") (pintype "passive"))
    )
    (net (code "145") (name "15V") (class "Default")
      (node (ref "R41") (pin "1") (pinfunction "1_1") (pintype "passive"))
      (node (ref "R42") (pin "1") (pinfunction "1_1") (pintype "passive"))
      (node (ref "R43") (pin "1") (pinfunction "1_1") (pintype "passive"))
      (node (ref "R44") (pin "1") (pinfunction "1_1") (pintype "passive"))
      (node (ref "R45") (pin "1") (pinfunction "1_1") (pintype "passive"))
      (node (ref "R46") (pin "1") (pinfunction "1_1") (pintype "passive"))
      (node (ref "R47") (pin "1") (pinfunction "1_1") (pintype "passive"))
      (node (ref "R48") (pin "1") (pinfunction "1_1") (pintype "passive"))
      (node (ref "R49") (pin "1") (pinfunction "1_1") (pintype "passive"))
      (node (ref "R50") (pin "1") (pinfunction "1_1") (pintype "passive"))
      (node (ref "R51") (pin "1") (pinfunction "1_1") (pintype "passive"))
      (node (ref "R52") (pin "1") (pinfunction "1_1") (pintype "passive"))
      (node (ref "R53") (pin "1") (pinfunction "1_1") (pintype "passive"))
      (node (ref "R54") (pin "1") (pinfunction "1_1") (pintype "passive"))
      (node (ref "R55") (pin "1") (pinfunction "1_1") (pintype "passive"))
      (node (ref "R56") (pin "1") (pinfunction "1_1") (pintype "passive"))
      (node (ref "R57") (pin "1") (pinfunction "1_1") (pintype "passive"))
      (node (ref "R58") (pin "1") (pinfunction "1_1") (pintype "passive"))
      (node (ref "R59") (pin "1") (pinfunction "1_1") (pintype "passive"))
      (node (ref "R60") (pin "1") (pinfunction "1_1") (pintype "passive"))
      (node (ref "R61") (pin "1") (pinfunction "1_1") (pintype "passive"))
      (node (ref "R62") (pin "1") (pinfunction "1_1") (pintype "passive"))
      (node (ref "R63") (pin "1") (pinfunction "1_1") (pintype "passive"))
      (node (ref "R64") (pin "1") (pinfunction "1_1") (pintype "passive"))
    )
    (net (code "146") (name "Net-(D6-A1)") (class "Default")
      (node (ref "D6") (pin "1") (pinfunction "A1_1") (pintype "passive"))
      (node (ref "R41") (pin "2") (pinfunction "2_2") (pintype "passive"))
    )
    (net (code "147") (name "Net-(D7-A1)") (class "Default")
      (node (ref "D7") (pin "1") (pinfunction "A1_1") (pintype "passive"))
      (node (ref "R42") (pin "2") (pinfunction "2_2") (pintype "passive"))
    )
    (net (code "148") (name "Net-(D8-A1)") (class "Default")
      (node (ref "D8") (pin "1") (pinfunction "A1_1") (pintype "passive"))
      (node (ref "R43") (pin "2") (pinfunction "2_2") (pintype "passive"))
    )
    (net (code "149") (name "Net-(D9-A1)") (class "Default")
      (node (ref "D9") (pin "1") (pinfunction "A1_1") (pintype "passive"))
      (node (ref "R44") (pin "2") (pinfunction "2_2") (pintype "passive"))
    )
    (net (code "150") (name "Net-(D10-A1)") (class "Default")
      (node (ref "D10") (pin "1") (pinfunction "A1_1") (pintype "passive"))
      (node (ref "R45") (pin "2") (pinfunction "2_2") (pintype "passive"))
    )
    (net (code "151") (name "Net-(D11-A1)") (class "Default")
      (node (ref "D11") (pin "1") (pinfunction "A1_1") (pintype "passive"))
      (node (ref "R46") (pin "2") (pinfunction "2_2") (pintype "passive"))
    )
    (net (code "152") (name "Net-(D12-A1)") (class "Default")
      (node (ref "D12") (pin "1") (pinfunction "A1_1") (pintype "passive"))
      (node (ref "R47") (pin "2") (pinfunction "2_2") (pintype "passive"))
    )
    (net (code "153") (name "Net-(D13-A1)") (class "Default")
      (node (ref "D13") (pin "1") (pinfunction "A1_1") (pintype "passive"))
      (node (ref "R48") (pin "2") (pinfunction "2_2") (pintype "passive"))
    )
    (net (code "154") (name "Net-(D14-A1)") (class "Default")
      (node (ref "D14") (pin "1") (pinfunction "A1_1") (pintype "passive"))
      (node (ref "R49") (pin "2") (pinfunction "2_2") (pintype "passive"))
    )
    (net (code "155") (name "Net-(D15-A1)") (class "Default")
      (node (ref "D15") (pin "1") (pinfunction "A1_1") (pintype "passive"))
      (node (ref "R50") (pin "2") (pinfunction "2_2") (pintype "passive"))
    )
    (net (code "156") (name "Net-(D16-A1)") (class "Default")
      (node (ref "D16") (pin "1") (pinfunction "A1_1") (pintype "passive"))
      (node (ref "R51") (pin "2") (pinfunction "2_2") (pintype "passive"))
    )
    (net (code "157") (name "Net-(D17-A1)") (class "Default")
      (node (ref "D17") (pin "1") (pinfunction "A1_1") (pintype "passive"))
      (node (ref "R52") (pin "2") (pinfunction "2_2") (pintype "passive"))
    )
    (net (code "158") (name "Net-(D18-A1)") (class "Default")
      (node (ref "D18") (pin "1") (pinfunction "A1_1") (pintype "passive"))
      (node (ref "R53") (pin "2") (pinfunction "2_2") (pintype "passive"))
    )
    (net (code "159") (name "Net-(D19-A1)") (class "Default")
      (node (ref "D19") (pin "1") (pinfunction "A1_1") (pintype "passive"))
      (node (ref "R54") (pin "2") (pinfunction "2_2") (pintype "passive"))
    )
    (net (code "160") (name "Net-(D20-A1)") (class "Default")
      (node (ref "D20") (pin "1") (pinfunction "A1_1") (pintype "passive"))
      (node (ref "R55") (pin "2") (pinfunction "2_2") (pintype "passive"))
    )
    (net (code "161") (name "Net-(D21-A1)") (class "Default")
      (node (ref "D21") (pin "1") (pinfunction "A1_1") (pintype "passive"))
      (node (ref "R56") (pin "2") (pinfunction "2_2") (pintype "passive"))
    )
    (net (code "162") (name "Net-(D22-A1)") (class "Default")
      (node (ref "D22") (pin "1") (pinfunction "A1_1") (pintype "passive"))
      (node (ref "R57") (pin "2") (pinfunction "2_2") (pintype "passive"))
    )
    (net (code "163") (name "Net-(D23-A1)") (class "Default")
      (node (ref "D23") (pin "1") (pinfunction "A1_1") (pintype "passive"))
      (node (ref "R58") (pin "2") (pinfunction "2_2") (pintype "passive"))
    )
    (net (code "164") (name "Net-(D24-A1)") (class "Default")
      (node (ref "D24") (pin "1") (pinfunction "A1_1") (pintype "passive"))
      (node (ref "R59") (pin "2") (pinfunction "2_2") (pintype "passive"))
    )
    (net (code "165") (name "Net-(D25-A1)") (class "Default")
      (node (ref "D25") (pin "1") (pinfunction "A1_1") (pintype "passive"))
      (node (ref "R60") (pin "2") (pinfunction "2_2") (pintype "passive"))
    )
    (net (code "166") (name "Net-(D26-A1)") (class "Default")
      (node (ref "D26") (pin "1") (pinfunction "A1_1") (pintype "passive"))
      (node (ref "R61") (pin "2") (pinfunction "2_2") (pintype "passive"))
    )
    (net (code "167") (name "Net-(D27-A1)") (class "Default")
      (node (ref "D27") (pin "1") (pinfunction "A1_1") (pintype "passive"))
      (node (ref "R62") (pin "2") (pinfunction "2_2") (pintype "passive"))
    )
    (net (code "168") (name "Net-(D28-A1)") (class "Default")
      (node (ref "D28") (pin "1") (pinfunction "A1_1") (pintype "passive"))
      (node (ref "R63") (pin "2") (pinfunction "2_2") (pintype "passive"))
    )
    (net (code "169") (name "Net-(D29-A1)") (class "Default")
      (node (ref "D29") (pin "1") (pinfunction "A1_1") (pintype "passive"))
      (node (ref "R64") (pin "2") (pinfunction "2_2") (pintype "passive"))
    )
  )
)
